# FetchControllerV2R2.net
KiCad netlist of a schematic drawn in EAGLE
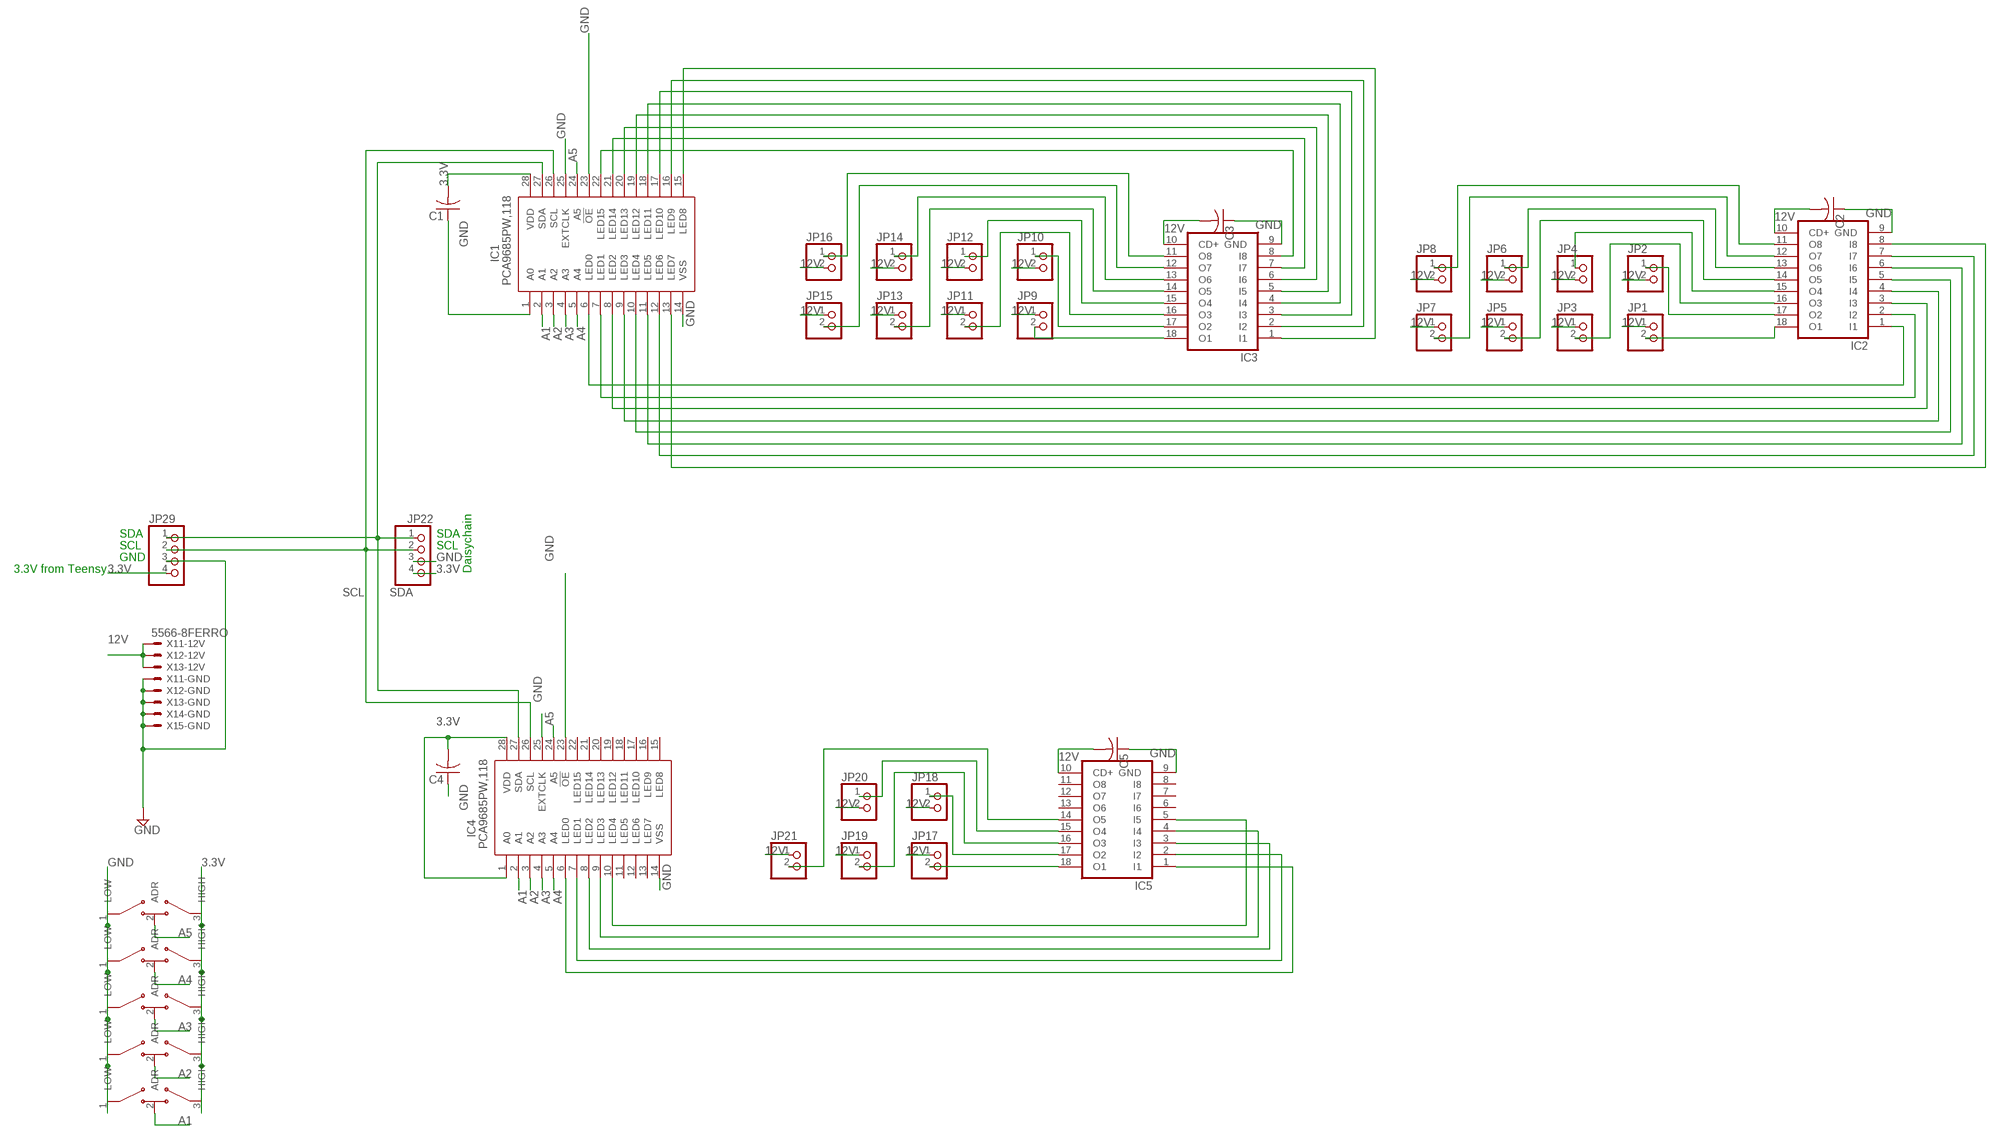
[diagram p0: schematic, sheet 1]

(export (version "E")
  (design (tool "Eeschema 10.0.6"))
  (components
    (comp (ref "C1")
      (value "C-USC0603")
      (footprint "eagle-import:C0603")
      (libsource (lib "eagle-import") (part "C-USC0603"))
    )
    (comp (ref "C2")
      (value "C-USC0603")
      (footprint "eagle-import:C0603")
      (libsource (lib "eagle-import") (part "C-USC0603"))
    )
    (comp (ref "C3")
      (value "C-USC0603")
      (footprint "eagle-import:C0603")
      (libsource (lib "eagle-import") (part "C-USC0603"))
    )
    (comp (ref "C4")
      (value "C-USC0603")
      (footprint "eagle-import:C0603")
      (libsource (lib "eagle-import") (part "C-USC0603"))
    )
    (comp (ref "C5")
      (value "C-USC0603")
      (footprint "eagle-import:C0603")
      (libsource (lib "eagle-import") (part "C-USC0603"))
    )
    (comp (ref "IC1")
      (value "PCA9685PW,118")
      (footprint "eagle-import:SOP65P640X110-28N")
      (fields (field (name "MOUSER_PART_NUMBER") "771-PCA9685PW,118"))
      (libsource (lib "eagle-import") (part "PCA9685PW,118"))
    )
    (comp (ref "IC2")
      (value "ULN2803ASMT")
      (footprint "eagle-import:SO18W")
      (libsource (lib "eagle-import") (part "ULN2803ASMT"))
    )
    (comp (ref "IC3")
      (value "ULN2803ASMT")
      (footprint "eagle-import:SO18W")
      (libsource (lib "eagle-import") (part "ULN2803ASMT"))
    )
    (comp (ref "IC4")
      (value "PCA9685PW,118")
      (footprint "eagle-import:SOP65P640X110-28N")
      (fields (field (name "MOUSER_PART_NUMBER") "771-PCA9685PW,118"))
      (libsource (lib "eagle-import") (part "PCA9685PW,118"))
    )
    (comp (ref "IC5")
      (value "ULN2803ASMT")
      (footprint "eagle-import:SO18W")
      (libsource (lib "eagle-import") (part "ULN2803ASMT"))
    )
    (comp (ref "JP1")
      (value "PINHD-1X2SOLENOID-R")
      (footprint "eagle-import:SOLENOID-CONTACT-REVERSE")
      (libsource (lib "eagle-import") (part "PINHD-1X2SOLENOID-R"))
    )
    (comp (ref "JP2")
      (value "PINHD-1X2SOLENOID")
      (footprint "eagle-import:SOLENOID-CONTACT")
      (libsource (lib "eagle-import") (part "PINHD-1X2SOLENOID"))
    )
    (comp (ref "JP3")
      (value "PINHD-1X2SOLENOID-R")
      (footprint "eagle-import:SOLENOID-CONTACT-REVERSE")
      (libsource (lib "eagle-import") (part "PINHD-1X2SOLENOID-R"))
    )
    (comp (ref "JP4")
      (value "PINHD-1X2SOLENOID")
      (footprint "eagle-import:SOLENOID-CONTACT")
      (libsource (lib "eagle-import") (part "PINHD-1X2SOLENOID"))
    )
    (comp (ref "JP5")
      (value "PINHD-1X2SOLENOID-R")
      (footprint "eagle-import:SOLENOID-CONTACT-REVERSE")
      (libsource (lib "eagle-import") (part "PINHD-1X2SOLENOID-R"))
    )
    (comp (ref "JP6")
      (value "PINHD-1X2SOLENOID")
      (footprint "eagle-import:SOLENOID-CONTACT")
      (libsource (lib "eagle-import") (part "PINHD-1X2SOLENOID"))
    )
    (comp (ref "JP7")
      (value "PINHD-1X2SOLENOID-R")
      (footprint "eagle-import:SOLENOID-CONTACT-REVERSE")
      (libsource (lib "eagle-import") (part "PINHD-1X2SOLENOID-R"))
    )
    (comp (ref "JP8")
      (value "PINHD-1X2SOLENOID")
      (footprint "eagle-import:SOLENOID-CONTACT")
      (libsource (lib "eagle-import") (part "PINHD-1X2SOLENOID"))
    )
    (comp (ref "JP9")
      (value "PINHD-1X2SOLENOID-R")
      (footprint "eagle-import:SOLENOID-CONTACT-REVERSE")
      (libsource (lib "eagle-import") (part "PINHD-1X2SOLENOID-R"))
    )
    (comp (ref "JP10")
      (value "PINHD-1X2SOLENOID")
      (footprint "eagle-import:SOLENOID-CONTACT")
      (libsource (lib "eagle-import") (part "PINHD-1X2SOLENOID"))
    )
    (comp (ref "JP11")
      (value "PINHD-1X2SOLENOID-R")
      (footprint "eagle-import:SOLENOID-CONTACT-REVERSE")
      (libsource (lib "eagle-import") (part "PINHD-1X2SOLENOID-R"))
    )
    (comp (ref "JP12")
      (value "PINHD-1X2SOLENOID")
      (footprint "eagle-import:SOLENOID-CONTACT")
      (libsource (lib "eagle-import") (part "PINHD-1X2SOLENOID"))
    )
    (comp (ref "JP13")
      (value "PINHD-1X2SOLENOID-R")
      (footprint "eagle-import:SOLENOID-CONTACT-REVERSE")
      (libsource (lib "eagle-import") (part "PINHD-1X2SOLENOID-R"))
    )
    (comp (ref "JP14")
      (value "PINHD-1X2SOLENOID")
      (footprint "eagle-import:SOLENOID-CONTACT")
      (libsource (lib "eagle-import") (part "PINHD-1X2SOLENOID"))
    )
    (comp (ref "JP15")
      (value "PINHD-1X2SOLENOID-R")
      (footprint "eagle-import:SOLENOID-CONTACT-REVERSE")
      (libsource (lib "eagle-import") (part "PINHD-1X2SOLENOID-R"))
    )
    (comp (ref "JP16")
      (value "PINHD-1X2SOLENOID")
      (footprint "eagle-import:SOLENOID-CONTACT")
      (libsource (lib "eagle-import") (part "PINHD-1X2SOLENOID"))
    )
    (comp (ref "JP17")
      (value "PINHD-1X2SOLENOID-R")
      (footprint "eagle-import:SOLENOID-CONTACT-REVERSE")
      (libsource (lib "eagle-import") (part "PINHD-1X2SOLENOID-R"))
    )
    (comp (ref "JP18")
      (value "PINHD-1X2SOLENOID")
      (footprint "eagle-import:SOLENOID-CONTACT")
      (libsource (lib "eagle-import") (part "PINHD-1X2SOLENOID"))
    )
    (comp (ref "JP19")
      (value "PINHD-1X2SOLENOID-R")
      (footprint "eagle-import:SOLENOID-CONTACT-REVERSE")
      (libsource (lib "eagle-import") (part "PINHD-1X2SOLENOID-R"))
    )
    (comp (ref "JP20")
      (value "PINHD-1X2SOLENOID")
      (footprint "eagle-import:SOLENOID-CONTACT")
      (libsource (lib "eagle-import") (part "PINHD-1X2SOLENOID"))
    )
    (comp (ref "JP21")
      (value "PINHD-1X2SOLENOID-R")
      (footprint "eagle-import:SOLENOID-CONTACT-REVERSE")
      (libsource (lib "eagle-import") (part "PINHD-1X2SOLENOID-R"))
    )
    (comp (ref "JP22")
      (value "PINHD-1X4")
      (footprint "eagle-import:1X04")
      (libsource (lib "eagle-import") (part "PINHD-1X4"))
    )
    (comp (ref "JP29")
      (value "PINHD-1X4")
      (footprint "eagle-import:1X04")
      (libsource (lib "eagle-import") (part "PINHD-1X4"))
    )
    (comp (ref "U$1")
      (value "ADR-SELECT")
      (footprint "eagle-import:ADR-SELECT-SOLDER")
      (libsource (lib "eagle-import") (part "ADR-SELECT"))
    )
    (comp (ref "U$2")
      (value "ADR-SELECT")
      (footprint "eagle-import:ADR-SELECT-SOLDER")
      (libsource (lib "eagle-import") (part "ADR-SELECT"))
    )
    (comp (ref "U$3")
      (value "ADR-SELECT")
      (footprint "eagle-import:ADR-SELECT-SOLDER")
      (libsource (lib "eagle-import") (part "ADR-SELECT"))
    )
    (comp (ref "U$4")
      (value "ADR-SELECT")
      (footprint "eagle-import:ADR-SELECT-SOLDER")
      (libsource (lib "eagle-import") (part "ADR-SELECT"))
    )
    (comp (ref "U$5")
      (value "ADR-SELECT")
      (footprint "eagle-import:ADR-SELECT-SOLDER")
      (libsource (lib "eagle-import") (part "ADR-SELECT"))
    )
    (comp (ref "X1")
      (value "5566-8FERRO")
      (footprint "eagle-import:5566-8-CLEAN")
      (libsource (lib "eagle-import") (part "5566-8FERRO"))
    )
  )
  (nets
    (net (code "1") (name "/3.3V") (class "Default")
      (node (ref "C1") (pin "2") (pinfunction "2_2") (pintype "passive"))
      (node (ref "C4") (pin "2") (pinfunction "2_2") (pintype "passive"))
      (node (ref "IC1") (pin "28") (pinfunction "VDD_28") (pintype "bidirectional"))
      (node (ref "IC4") (pin "1") (pinfunction "A0_1") (pintype "bidirectional"))
      (node (ref "IC4") (pin "28") (pinfunction "VDD_28") (pintype "bidirectional"))
      (node (ref "JP22") (pin "4") (pinfunction "4_4") (pintype "passive"))
      (node (ref "JP29") (pin "4") (pinfunction "4_4") (pintype "passive"))
      (node (ref "U$1") (pin "3") (pinfunction "HIGH_3") (pintype "bidirectional"))
      (node (ref "U$2") (pin "3") (pinfunction "HIGH_3") (pintype "bidirectional"))
      (node (ref "U$3") (pin "3") (pinfunction "HIGH_3") (pintype "bidirectional"))
      (node (ref "U$4") (pin "3") (pinfunction "HIGH_3") (pintype "bidirectional"))
      (node (ref "U$5") (pin "3") (pinfunction "HIGH_3") (pintype "bidirectional"))
    )
    (net (code "2") (name "/12V") (class "Default")
      (node (ref "C2") (pin "2") (pinfunction "2_2") (pintype "passive"))
      (node (ref "C3") (pin "2") (pinfunction "2_2") (pintype "passive"))
      (node (ref "C5") (pin "2") (pinfunction "2_2") (pintype "passive"))
      (node (ref "IC2") (pin "10") (pinfunction "CD+_10") (pintype "passive"))
      (node (ref "IC3") (pin "10") (pinfunction "CD+_10") (pintype "passive"))
      (node (ref "IC5") (pin "10") (pinfunction "CD+_10") (pintype "passive"))
      (node (ref "JP1") (pin "1") (pinfunction "1_1") (pintype "passive"))
      (node (ref "JP10") (pin "2") (pinfunction "2_2") (pintype "passive"))
      (node (ref "JP11") (pin "1") (pinfunction "1_1") (pintype "passive"))
      (node (ref "JP12") (pin "2") (pinfunction "2_2") (pintype "passive"))
      (node (ref "JP13") (pin "1") (pinfunction "1_1") (pintype "passive"))
      (node (ref "JP14") (pin "2") (pinfunction "2_2") (pintype "passive"))
      (node (ref "JP15") (pin "1") (pinfunction "1_1") (pintype "passive"))
      (node (ref "JP16") (pin "2") (pinfunction "2_2") (pintype "passive"))
      (node (ref "JP17") (pin "1") (pinfunction "1_1") (pintype "passive"))
      (node (ref "JP18") (pin "2") (pinfunction "2_2") (pintype "passive"))
      (node (ref "JP19") (pin "1") (pinfunction "1_1") (pintype "passive"))
      (node (ref "JP2") (pin "2") (pinfunction "2_2") (pintype "passive"))
      (node (ref "JP20") (pin "2") (pinfunction "2_2") (pintype "passive"))
      (node (ref "JP21") (pin "1") (pinfunction "1_1") (pintype "passive"))
      (node (ref "JP3") (pin "1") (pinfunction "1_1") (pintype "passive"))
      (node (ref "JP4") (pin "2") (pinfunction "2_2") (pintype "passive"))
      (node (ref "JP5") (pin "1") (pinfunction "1_1") (pintype "passive"))
      (node (ref "JP6") (pin "2") (pinfunction "2_2") (pintype "passive"))
      (node (ref "JP7") (pin "1") (pinfunction "1_1") (pintype "passive"))
      (node (ref "JP8") (pin "2") (pinfunction "2_2") (pintype "passive"))
      (node (ref "JP9") (pin "1") (pinfunction "1_1") (pintype "passive"))
      (node (ref "X1") (pin "1") (pinfunction "S_1") (pintype "passive"))
      (node (ref "X1") (pin "2") (pinfunction "S_2") (pintype "passive"))
      (node (ref "X1") (pin "3") (pinfunction "S_3") (pintype "passive"))
    )
    (net (code "3") (name "/A1") (class "Default")
      (node (ref "IC1") (pin "2") (pinfunction "A1_2") (pintype "bidirectional"))
      (node (ref "IC4") (pin "2") (pinfunction "A1_2") (pintype "bidirectional"))
      (node (ref "U$5") (pin "2") (pinfunction "ADR_2") (pintype "bidirectional"))
    )
    (net (code "4") (name "/A2") (class "Default")
      (node (ref "IC1") (pin "3") (pinfunction "A2_3") (pintype "bidirectional"))
      (node (ref "IC4") (pin "3") (pinfunction "A2_3") (pintype "bidirectional"))
      (node (ref "U$4") (pin "2") (pinfunction "ADR_2") (pintype "bidirectional"))
    )
    (net (code "5") (name "/A3") (class "Default")
      (node (ref "IC1") (pin "4") (pinfunction "A3_4") (pintype "bidirectional"))
      (node (ref "IC4") (pin "4") (pinfunction "A3_4") (pintype "bidirectional"))
      (node (ref "U$3") (pin "2") (pinfunction "ADR_2") (pintype "bidirectional"))
    )
    (net (code "6") (name "/A4") (class "Default")
      (node (ref "IC1") (pin "5") (pinfunction "A4_5") (pintype "bidirectional"))
      (node (ref "IC4") (pin "5") (pinfunction "A4_5") (pintype "bidirectional"))
      (node (ref "U$2") (pin "2") (pinfunction "ADR_2") (pintype "bidirectional"))
    )
    (net (code "7") (name "/A5") (class "Default")
      (node (ref "IC1") (pin "24") (pinfunction "A5_24") (pintype "bidirectional"))
      (node (ref "IC4") (pin "24") (pinfunction "A5_24") (pintype "bidirectional"))
      (node (ref "U$1") (pin "2") (pinfunction "ADR_2") (pintype "bidirectional"))
    )
    (net (code "8") (name "/SCL") (class "Default")
      (node (ref "IC1") (pin "26") (pinfunction "SCL_26") (pintype "bidirectional"))
      (node (ref "IC4") (pin "26") (pinfunction "SCL_26") (pintype "bidirectional"))
      (node (ref "JP22") (pin "2") (pinfunction "2_2") (pintype "passive"))
      (node (ref "JP29") (pin "2") (pinfunction "2_2") (pintype "passive"))
    )
    (net (code "9") (name "/SDA") (class "Default")
      (node (ref "IC1") (pin "27") (pinfunction "SDA_27") (pintype "bidirectional"))
      (node (ref "IC4") (pin "27") (pinfunction "SDA_27") (pintype "bidirectional"))
      (node (ref "JP22") (pin "1") (pinfunction "1_1") (pintype "passive"))
      (node (ref "JP29") (pin "1") (pinfunction "1_1") (pintype "passive"))
    )
    (net (code "10") (name "GND") (class "Default")
      (node (ref "C1") (pin "1") (pinfunction "1_1") (pintype "passive"))
      (node (ref "C2") (pin "1") (pinfunction "1_1") (pintype "passive"))
      (node (ref "C3") (pin "1") (pinfunction "1_1") (pintype "passive"))
      (node (ref "C4") (pin "1") (pinfunction "1_1") (pintype "passive"))
      (node (ref "C5") (pin "1") (pinfunction "1_1") (pintype "passive"))
      (node (ref "IC1") (pin "1") (pinfunction "A0_1") (pintype "bidirectional"))
      (node (ref "IC1") (pin "14") (pinfunction "VSS_14") (pintype "bidirectional"))
      (node (ref "IC1") (pin "23") (pinfunction "~{OE}_23") (pintype "bidirectional"))
      (node (ref "IC1") (pin "25") (pinfunction "EXTCLK_25") (pintype "bidirectional"))
      (node (ref "IC2") (pin "9") (pinfunction "GND_9") (pintype "power_in"))
      (node (ref "IC3") (pin "9") (pinfunction "GND_9") (pintype "power_in"))
      (node (ref "IC4") (pin "14") (pinfunction "VSS_14") (pintype "bidirectional"))
      (node (ref "IC4") (pin "23") (pinfunction "~{OE}_23") (pintype "bidirectional"))
      (node (ref "IC4") (pin "25") (pinfunction "EXTCLK_25") (pintype "bidirectional"))
      (node (ref "IC5") (pin "9") (pinfunction "GND_9") (pintype "power_in"))
      (node (ref "JP22") (pin "3") (pinfunction "3_3") (pintype "passive"))
      (node (ref "JP29") (pin "3") (pinfunction "3_3") (pintype "passive"))
      (node (ref "U$1") (pin "1") (pinfunction "LOW_1") (pintype "bidirectional"))
      (node (ref "U$2") (pin "1") (pinfunction "LOW_1") (pintype "bidirectional"))
      (node (ref "U$3") (pin "1") (pinfunction "LOW_1") (pintype "bidirectional"))
      (node (ref "U$4") (pin "1") (pinfunction "LOW_1") (pintype "bidirectional"))
      (node (ref "U$5") (pin "1") (pinfunction "LOW_1") (pintype "bidirectional"))
      (node (ref "X1") (pin "4") (pinfunction "S_4") (pintype "passive"))
      (node (ref "X1") (pin "5") (pinfunction "S_5") (pintype "passive"))
      (node (ref "X1") (pin "6") (pinfunction "S_6") (pintype "passive"))
      (node (ref "X1") (pin "7") (pinfunction "S_7") (pintype "passive"))
      (node (ref "X1") (pin "8") (pinfunction "S_8") (pintype "passive"))
    )
    (net (code "11") (name "Net-(IC1-LED0)") (class "Default")
      (node (ref "IC1") (pin "6") (pinfunction "LED0_6") (pintype "bidirectional"))
      (node (ref "IC2") (pin "1") (pinfunction "I1_1") (pintype "input"))
    )
    (net (code "12") (name "Net-(IC1-LED1)") (class "Default")
      (node (ref "IC1") (pin "7") (pinfunction "LED1_7") (pintype "bidirectional"))
      (node (ref "IC2") (pin "2") (pinfunction "I2_2") (pintype "input"))
    )
    (net (code "13") (name "Net-(IC1-LED2)") (class "Default")
      (node (ref "IC1") (pin "8") (pinfunction "LED2_8") (pintype "bidirectional"))
      (node (ref "IC2") (pin "3") (pinfunction "I3_3") (pintype "input"))
    )
    (net (code "14") (name "Net-(IC1-LED3)") (class "Default")
      (node (ref "IC1") (pin "9") (pinfunction "LED3_9") (pintype "bidirectional"))
      (node (ref "IC2") (pin "4") (pinfunction "I4_4") (pintype "input"))
    )
    (net (code "15") (name "Net-(IC1-LED4)") (class "Default")
      (node (ref "IC1") (pin "10") (pinfunction "LED4_10") (pintype "bidirectional"))
      (node (ref "IC2") (pin "5") (pinfunction "I5_5") (pintype "input"))
    )
    (net (code "16") (name "Net-(IC1-LED5)") (class "Default")
      (node (ref "IC1") (pin "11") (pinfunction "LED5_11") (pintype "bidirectional"))
      (node (ref "IC2") (pin "6") (pinfunction "I6_6") (pintype "input"))
    )
    (net (code "17") (name "Net-(IC1-LED6)") (class "Default")
      (node (ref "IC1") (pin "12") (pinfunction "LED6_12") (pintype "bidirectional"))
      (node (ref "IC2") (pin "7") (pinfunction "I7_7") (pintype "input"))
    )
    (net (code "18") (name "Net-(IC1-LED7)") (class "Default")
      (node (ref "IC1") (pin "13") (pinfunction "LED7_13") (pintype "bidirectional"))
      (node (ref "IC2") (pin "8") (pinfunction "I8_8") (pintype "input"))
    )
    (net (code "19") (name "Net-(IC1-LED8)") (class "Default")
      (node (ref "IC1") (pin "15") (pinfunction "LED8_15") (pintype "bidirectional"))
      (node (ref "IC3") (pin "1") (pinfunction "I1_1") (pintype "input"))
    )
    (net (code "20") (name "Net-(IC1-LED9)") (class "Default")
      (node (ref "IC1") (pin "16") (pinfunction "LED9_16") (pintype "bidirectional"))
      (node (ref "IC3") (pin "2") (pinfunction "I2_2") (pintype "input"))
    )
    (net (code "21") (name "Net-(IC1-LED10)") (class "Default")
      (node (ref "IC1") (pin "17") (pinfunction "LED10_17") (pintype "bidirectional"))
      (node (ref "IC3") (pin "3") (pinfunction "I3_3") (pintype "input"))
    )
    (net (code "22") (name "Net-(IC1-LED11)") (class "Default")
      (node (ref "IC1") (pin "18") (pinfunction "LED11_18") (pintype "bidirectional"))
      (node (ref "IC3") (pin "4") (pinfunction "I4_4") (pintype "input"))
    )
    (net (code "23") (name "Net-(IC1-LED12)") (class "Default")
      (node (ref "IC1") (pin "19") (pinfunction "LED12_19") (pintype "bidirectional"))
      (node (ref "IC3") (pin "5") (pinfunction "I5_5") (pintype "input"))
    )
    (net (code "24") (name "Net-(IC1-LED13)") (class "Default")
      (node (ref "IC1") (pin "20") (pinfunction "LED13_20") (pintype "bidirectional"))
      (node (ref "IC3") (pin "6") (pinfunction "I6_6") (pintype "input"))
    )
    (net (code "25") (name "Net-(IC1-LED14)") (class "Default")
      (node (ref "IC1") (pin "21") (pinfunction "LED14_21") (pintype "bidirectional"))
      (node (ref "IC3") (pin "7") (pinfunction "I7_7") (pintype "input"))
    )
    (net (code "26") (name "Net-(IC1-LED15)") (class "Default")
      (node (ref "IC1") (pin "22") (pinfunction "LED15_22") (pintype "bidirectional"))
      (node (ref "IC3") (pin "8") (pinfunction "I8_8") (pintype "input"))
    )
    (net (code "27") (name "Net-(IC2-O1)") (class "Default")
      (node (ref "IC2") (pin "18") (pinfunction "O1_18") (pintype "open_collector"))
      (node (ref "JP1") (pin "2") (pinfunction "2_2") (pintype "passive"))
    )
    (net (code "28") (name "Net-(IC2-O2)") (class "Default")
      (node (ref "IC2") (pin "17") (pinfunction "O2_17") (pintype "open_collector"))
      (node (ref "JP2") (pin "1") (pinfunction "1_1") (pintype "passive"))
    )
    (net (code "29") (name "Net-(IC2-O3)") (class "Default")
      (node (ref "IC2") (pin "16") (pinfunction "O3_16") (pintype "open_collector"))
      (node (ref "JP3") (pin "2") (pinfunction "2_2") (pintype "passive"))
    )
    (net (code "30") (name "Net-(IC2-O4)") (class "Default")
      (node (ref "IC2") (pin "15") (pinfunction "O4_15") (pintype "open_collector"))
      (node (ref "JP4") (pin "1") (pinfunction "1_1") (pintype "passive"))
    )
    (net (code "31") (name "Net-(IC2-O5)") (class "Default")
      (node (ref "IC2") (pin "14") (pinfunction "O5_14") (pintype "open_collector"))
      (node (ref "JP5") (pin "2") (pinfunction "2_2") (pintype "passive"))
    )
    (net (code "32") (name "Net-(IC2-O6)") (class "Default")
      (node (ref "IC2") (pin "13") (pinfunction "O6_13") (pintype "open_collector"))
      (node (ref "JP6") (pin "1") (pinfunction "1_1") (pintype "passive"))
    )
    (net (code "33") (name "Net-(IC2-O7)") (class "Default")
      (node (ref "IC2") (pin "12") (pinfunction "O7_12") (pintype "open_collector"))
      (node (ref "JP7") (pin "2") (pinfunction "2_2") (pintype "passive"))
    )
    (net (code "34") (name "Net-(IC2-O8)") (class "Default")
      (node (ref "IC2") (pin "11") (pinfunction "O8_11") (pintype "open_collector"))
      (node (ref "JP8") (pin "1") (pinfunction "1_1") (pintype "passive"))
    )
    (net (code "35") (name "Net-(IC3-O1)") (class "Default")
      (node (ref "IC3") (pin "18") (pinfunction "O1_18") (pintype "open_collector"))
      (node (ref "JP9") (pin "2") (pinfunction "2_2") (pintype "passive"))
    )
    (net (code "36") (name "Net-(IC3-O2)") (class "Default")
      (node (ref "IC3") (pin "17") (pinfunction "O2_17") (pintype "open_collector"))
      (node (ref "JP10") (pin "1") (pinfunction "1_1") (pintype "passive"))
    )
    (net (code "37") (name "Net-(IC3-O3)") (class "Default")
      (node (ref "IC3") (pin "16") (pinfunction "O3_16") (pintype "open_collector"))
      (node (ref "JP11") (pin "2") (pinfunction "2_2") (pintype "passive"))
    )
    (net (code "38") (name "Net-(IC3-O4)") (class "Default")
      (node (ref "IC3") (pin "15") (pinfunction "O4_15") (pintype "open_collector"))
      (node (ref "JP12") (pin "1") (pinfunction "1_1") (pintype "passive"))
    )
    (net (code "39") (name "Net-(IC3-O5)") (class "Default")
      (node (ref "IC3") (pin "14") (pinfunction "O5_14") (pintype "open_collector"))
      (node (ref "JP13") (pin "2") (pinfunction "2_2") (pintype "passive"))
    )
    (net (code "40") (name "Net-(IC3-O6)") (class "Default")
      (node (ref "IC3") (pin "13") (pinfunction "O6_13") (pintype "open_collector"))
      (node (ref "JP14") (pin "1") (pinfunction "1_1") (pintype "passive"))
    )
    (net (code "41") (name "Net-(IC3-O7)") (class "Default")
      (node (ref "IC3") (pin "12") (pinfunction "O7_12") (pintype "open_collector"))
      (node (ref "JP15") (pin "2") (pinfunction "2_2") (pintype "passive"))
    )
    (net (code "42") (name "Net-(IC3-O8)") (class "Default")
      (node (ref "IC3") (pin "11") (pinfunction "O8_11") (pintype "open_collector"))
      (node (ref "JP16") (pin "1") (pinfunction "1_1") (pintype "passive"))
    )
    (net (code "43") (name "Net-(IC4-LED0)") (class "Default")
      (node (ref "IC4") (pin "6") (pinfunction "LED0_6") (pintype "bidirectional"))
      (node (ref "IC5") (pin "1") (pinfunction "I1_1") (pintype "input"))
    )
    (net (code "44") (name "Net-(IC4-LED1)") (class "Default")
      (node (ref "IC4") (pin "7") (pinfunction "LED1_7") (pintype "bidirectional"))
      (node (ref "IC5") (pin "2") (pinfunction "I2_2") (pintype "input"))
    )
    (net (code "45") (name "Net-(IC4-LED2)") (class "Default")
      (node (ref "IC4") (pin "8") (pinfunction "LED2_8") (pintype "bidirectional"))
      (node (ref "IC5") (pin "3") (pinfunction "I3_3") (pintype "input"))
    )
    (net (code "46") (name "Net-(IC4-LED3)") (class "Default")
      (node (ref "IC4") (pin "9") (pinfunction "LED3_9") (pintype "bidirectional"))
      (node (ref "IC5") (pin "4") (pinfunction "I4_4") (pintype "input"))
    )
    (net (code "47") (name "Net-(IC4-LED4)") (class "Default")
      (node (ref "IC4") (pin "10") (pinfunction "LED4_10") (pintype "bidirectional"))
      (node (ref "IC5") (pin "5") (pinfunction "I5_5") (pintype "input"))
    )
    (net (code "48") (name "Net-(IC5-O1)") (class "Default")
      (node (ref "IC5") (pin "18") (pinfunction "O1_18") (pintype "open_collector"))
      (node (ref "JP17") (pin "2") (pinfunction "2_2") (pintype "passive"))
    )
    (net (code "49") (name "Net-(IC5-O2)") (class "Default")
      (node (ref "IC5") (pin "17") (pinfunction "O2_17") (pintype "open_collector"))
      (node (ref "JP18") (pin "1") (pinfunction "1_1") (pintype "passive"))
    )
    (net (code "50") (name "Net-(IC5-O3)") (class "Default")
      (node (ref "IC5") (pin "16") (pinfunction "O3_16") (pintype "open_collector"))
      (node (ref "JP19") (pin "2") (pinfunction "2_2") (pintype "passive"))
    )
    (net (code "51") (name "Net-(IC5-O4)") (class "Default")
      (node (ref "IC5") (pin "15") (pinfunction "O4_15") (pintype "open_collector"))
      (node (ref "JP20") (pin "1") (pinfunction "1_1") (pintype "passive"))
    )
    (net (code "52") (name "Net-(IC5-O5)") (class "Default")
      (node (ref "IC5") (pin "14") (pinfunction "O5_14") (pintype "open_collector"))
      (node (ref "JP21") (pin "2") (pinfunction "2_2") (pintype "passive"))
    )
    (net (code "53") (name "unconnected-(IC4-LED5-Pad11)") (class "Default")
      (node (ref "IC4") (pin "11") (pinfunction "LED5_11") (pintype "bidirectional"))
    )
    (net (code "54") (name "unconnected-(IC4-LED6-Pad12)") (class "Default")
      (node (ref "IC4") (pin "12") (pinfunction "LED6_12") (pintype "bidirectional"))
    )
    (net (code "55") (name "unconnected-(IC4-LED7-Pad13)") (class "Default")
      (node (ref "IC4") (pin "13") (pinfunction "LED7_13") (pintype "bidirectional"))
    )
    (net (code "56") (name "unconnected-(IC4-LED8-Pad15)") (class "Default")
      (node (ref "IC4") (pin "15") (pinfunction "LED8_15") (pintype "bidirectional"))
    )
    (net (code "57") (name "unconnected-(IC4-LED9-Pad16)") (class "Default")
      (node (ref "IC4") (pin "16") (pinfunction "LED9_16") (pintype "bidirectional"))
    )
    (net (code "58") (name "unconnected-(IC4-LED10-Pad17)") (class "Default")
      (node (ref "IC4") (pin "17") (pinfunction "LED10_17") (pintype "bidirectional"))
    )
    (net (code "59") (name "unconnected-(IC4-LED11-Pad18)") (class "Default")
      (node (ref "IC4") (pin "18") (pinfunction "LED11_18") (pintype "bidirectional"))
    )
    (net (code "60") (name "unconnected-(IC4-LED12-Pad19)") (class "Default")
      (node (ref "IC4") (pin "19") (pinfunction "LED12_19") (pintype "bidirectional"))
    )
    (net (code "61") (name "unconnected-(IC4-LED13-Pad20)") (class "Default")
      (node (ref "IC4") (pin "20") (pinfunction "LED13_20") (pintype "bidirectional"))
    )
    (net (code "62") (name "unconnected-(IC4-LED14-Pad21)") (class "Default")
      (node (ref "IC4") (pin "21") (pinfunction "LED14_21") (pintype "bidirectional"))
    )
    (net (code "63") (name "unconnected-(IC4-LED15-Pad22)") (class "Default")
      (node (ref "IC4") (pin "22") (pinfunction "LED15_22") (pintype "bidirectional"))
    )
    (net (code "64") (name "unconnected-(IC5-I6-Pad6)") (class "Default")
      (node (ref "IC5") (pin "6") (pinfunction "I6_6") (pintype "input"))
    )
    (net (code "65") (name "unconnected-(IC5-I7-Pad7)") (class "Default")
      (node (ref "IC5") (pin "7") (pinfunction "I7_7") (pintype "input"))
    )
    (net (code "66") (name "unconnected-(IC5-I8-Pad8)") (class "Default")
      (node (ref "IC5") (pin "8") (pinfunction "I8_8") (pintype "input"))
    )
    (net (code "67") (name "unconnected-(IC5-O6-Pad13)") (class "Default")
      (node (ref "IC5") (pin "13") (pinfunction "O6_13") (pintype "open_collector"))
    )
    (net (code "68") (name "unconnected-(IC5-O7-Pad12)") (class "Default")
      (node (ref "IC5") (pin "12") (pinfunction "O7_12") (pintype "open_collector"))
    )
    (net (code "69") (name "unconnected-(IC5-O8-Pad11)") (class "Default")
      (node (ref "IC5") (pin "11") (pinfunction "O8_11") (pintype "open_collector"))
    )
  )
)
